# dual-power.net
KiCad netlist of a schematic drawn in EAGLE
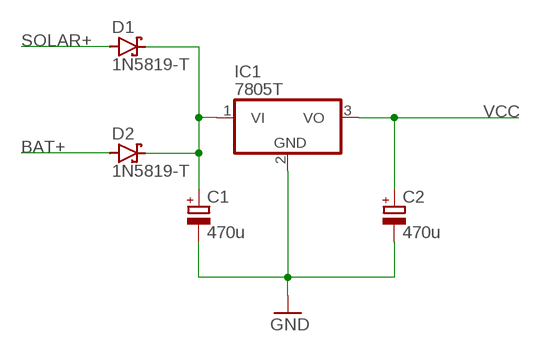
[diagram p0: schematic, sheet 1]

(export (version "E")
  (design (tool "Eeschema 10.0.6"))
  (components
    (comp (ref "C1")
      (value "470u")
      (footprint "eagle-import:E7,5-18")
      (libsource (lib "eagle-import") (part "CPOL-EUE7.5-18"))
    )
    (comp (ref "C2")
      (value "470u")
      (footprint "eagle-import:E7,5-18")
      (libsource (lib "eagle-import") (part "CPOL-EUE7.5-18"))
    )
    (comp (ref "D1")
      (value "1N5819-T")
      (footprint "eagle-import:DO41-7.6")
      (libsource (lib "eagle-import") (part "1N5819-T"))
    )
    (comp (ref "D2")
      (value "1N5819-T")
      (footprint "eagle-import:DO41-7.6")
      (libsource (lib "eagle-import") (part "1N5819-T"))
    )
    (comp (ref "IC1")
      (value "7805T")
      (footprint "eagle-import:TO220H")
      (libsource (lib "eagle-import") (part "78T05"))
    )
  )
  (nets
    (net (code "1") (name "/BAT+") (class "Default")
      (node (ref "D2") (pin "A") (pinfunction "A_A") (pintype "passive"))
    )
    (net (code "2") (name "/SOLAR+") (class "Default")
      (node (ref "D1") (pin "A") (pinfunction "A_A") (pintype "passive"))
    )
    (net (code "3") (name "/VCC") (class "Default")
      (node (ref "C2") (pin "+") (pinfunction "+_+") (pintype "passive"))
      (node (ref "IC1") (pin "3") (pinfunction "VO_3") (pintype "passive"))
    )
    (net (code "4") (name "GND") (class "Default")
      (node (ref "C1") (pin "-") (pinfunction "-_-") (pintype "passive"))
      (node (ref "C2") (pin "-") (pinfunction "-_-") (pintype "passive"))
      (node (ref "IC1") (pin "2") (pinfunction "GND_2") (pintype "passive"))
    )
    (net (code "5") (name "Net-(IC1-VI)") (class "Default")
      (node (ref "C1") (pin "+") (pinfunction "+_+") (pintype "passive"))
      (node (ref "D1") (pin "C") (pinfunction "C_C") (pintype "passive"))
      (node (ref "D2") (pin "C") (pinfunction "C_C") (pintype "passive"))
      (node (ref "IC1") (pin "1") (pinfunction "VI_1") (pintype "input"))
    )
  )
)
